# Board.net
KiCad netlist of a schematic drawn in EAGLE
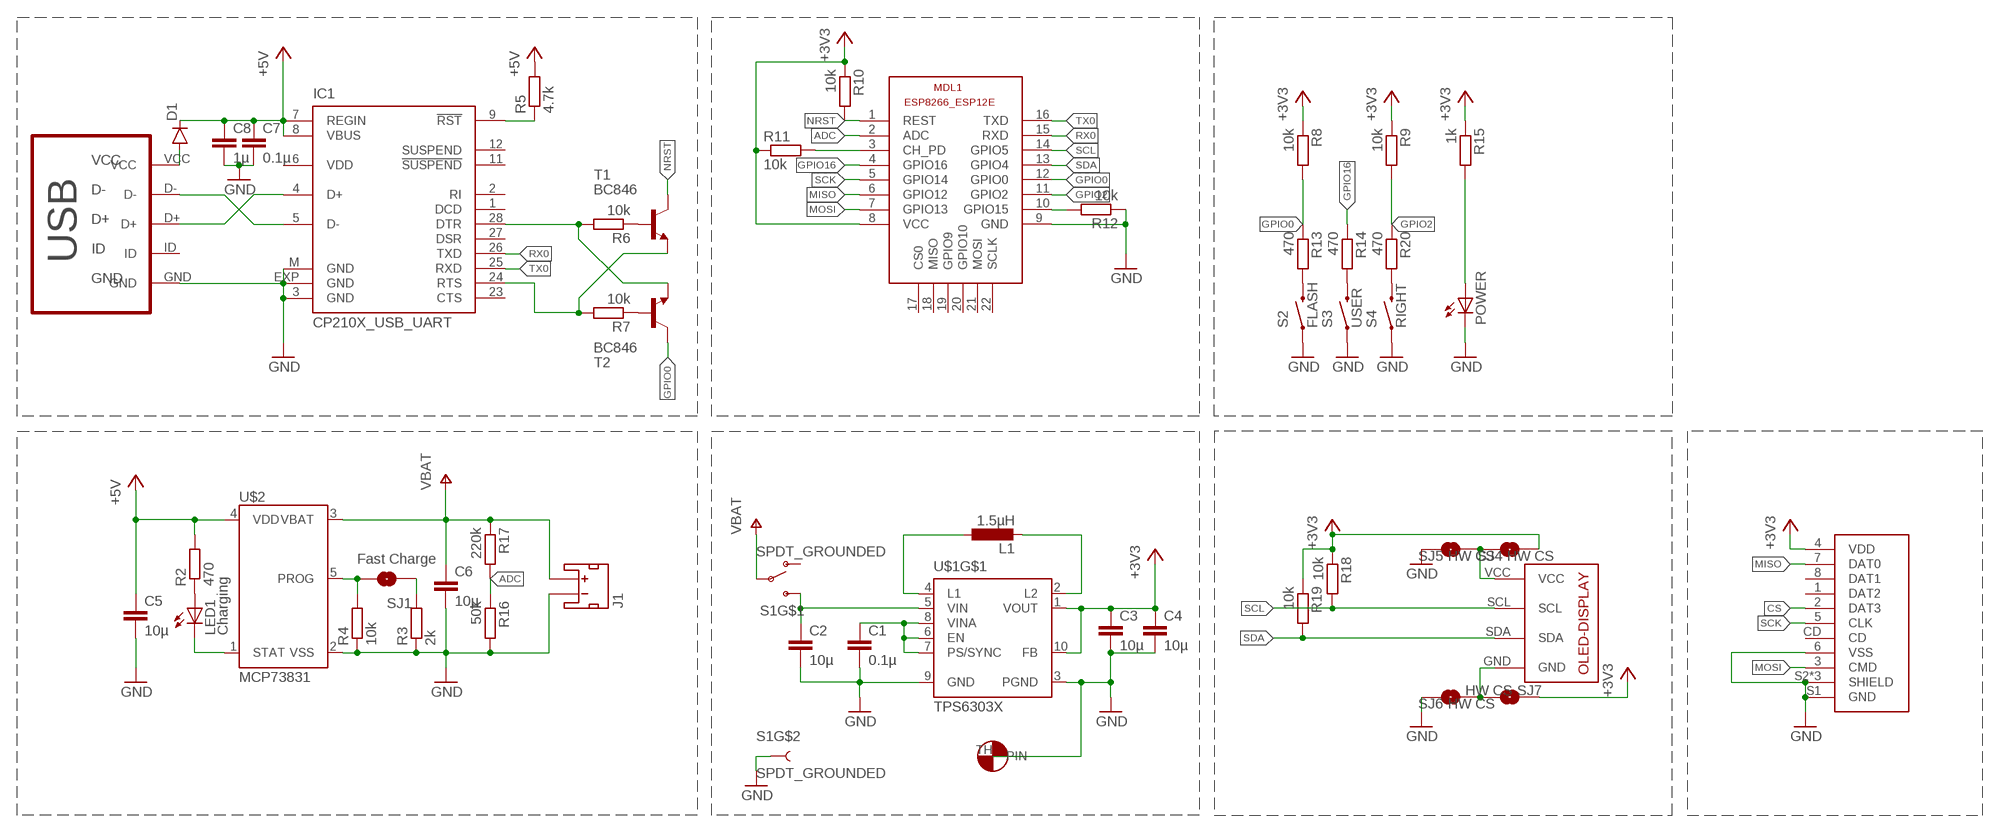
[diagram p0: schematic, sheet 1]

(export (version "E")
  (design (tool "Eeschema 10.0.6"))
  (components
    (comp (ref "C1")
      (value "0.1µ")
      (footprint "eagle-import:C0603")
      (libsource (lib "eagle-import") (part "C-EUC0603"))
    )
    (comp (ref "C2")
      (value "10µ")
      (footprint "eagle-import:C0603")
      (libsource (lib "eagle-import") (part "C-EUC0603"))
    )
    (comp (ref "C3")
      (value "10µ")
      (footprint "eagle-import:C0603")
      (libsource (lib "eagle-import") (part "C-EUC0603"))
    )
    (comp (ref "C4")
      (value "10µ")
      (footprint "eagle-import:C0603")
      (libsource (lib "eagle-import") (part "C-EUC0603"))
    )
    (comp (ref "C5")
      (value "10µ")
      (footprint "eagle-import:C0603")
      (libsource (lib "eagle-import") (part "C-EUC0603"))
    )
    (comp (ref "C6")
      (value "10µ")
      (footprint "eagle-import:C0603")
      (libsource (lib "eagle-import") (part "C-EUC0603"))
    )
    (comp (ref "C7")
      (value "0.1µ")
      (footprint "eagle-import:C0603")
      (libsource (lib "eagle-import") (part "C-EUC0603"))
    )
    (comp (ref "C8")
      (value "1µ")
      (footprint "eagle-import:C0603")
      (libsource (lib "eagle-import") (part "C-EUC0603"))
    )
    (comp (ref "D1")
      (value "DIODEBAS16")
      (footprint "eagle-import:SOD-323")
      (libsource (lib "eagle-import") (part "DIODEBAS16"))
    )
    (comp (ref "IC1")
      (value "CP210X_USB_UART")
      (footprint "eagle-import:MLP28")
      (libsource (lib "eagle-import") (part "CP210X_USB_UART"))
    )
    (comp (ref "J1")
      (value "JST_2MM_MALE")
      (footprint "eagle-import:JST-2-SMD")
      (libsource (lib "eagle-import") (part "JST_2MM_MALE"))
    )
    (comp (ref "L1")
      (value "1.5µH")
      (footprint "eagle-import:L3225P")
      (libsource (lib "eagle-import") (part "L-EUL3225P"))
    )
    (comp (ref "LED1")
      (value "Charging")
      (footprint "eagle-import:SML0805")
      (libsource (lib "eagle-import") (part "LEDSML0805"))
    )
    (comp (ref "MDL1")
      (value "ESP8266-12EESP8266-ESP12E")
      (footprint "eagle-import:ESP8266-ESP12E")
      (libsource (lib "eagle-import") (part "ESP8266-12EESP8266-ESP12E"))
    )
    (comp (ref "POWER")
      (value "LEDSML0805")
      (footprint "eagle-import:SML0805")
      (libsource (lib "eagle-import") (part "LEDSML0805"))
    )
    (comp (ref "R2")
      (value "470")
      (footprint "eagle-import:R0603")
      (libsource (lib "eagle-import") (part "R-EU_R0603"))
    )
    (comp (ref "R3")
      (value "2k")
      (footprint "eagle-import:R0603")
      (libsource (lib "eagle-import") (part "R-EU_R0603"))
    )
    (comp (ref "R4")
      (value "10k")
      (footprint "eagle-import:R0603")
      (libsource (lib "eagle-import") (part "R-EU_R0603"))
    )
    (comp (ref "R5")
      (value "4.7k")
      (footprint "eagle-import:R0603")
      (libsource (lib "eagle-import") (part "R-EU_R0603"))
    )
    (comp (ref "R6")
      (value "10k")
      (footprint "eagle-import:R0603")
      (libsource (lib "eagle-import") (part "R-EU_R0603"))
    )
    (comp (ref "R7")
      (value "10k")
      (footprint "eagle-import:R0603")
      (libsource (lib "eagle-import") (part "R-EU_R0603"))
    )
    (comp (ref "R8")
      (value "10k")
      (footprint "eagle-import:R0603")
      (libsource (lib "eagle-import") (part "R-EU_R0603"))
    )
    (comp (ref "R9")
      (value "10k")
      (footprint "eagle-import:R0603")
      (libsource (lib "eagle-import") (part "R-EU_R0603"))
    )
    (comp (ref "R10")
      (value "10k")
      (footprint "eagle-import:R0603")
      (libsource (lib "eagle-import") (part "R-EU_R0603"))
    )
    (comp (ref "R11")
      (value "10k")
      (footprint "eagle-import:R0603")
      (libsource (lib "eagle-import") (part "R-EU_R0603"))
    )
    (comp (ref "R12")
      (value "10k")
      (footprint "eagle-import:R0603")
      (libsource (lib "eagle-import") (part "R-EU_R0603"))
    )
    (comp (ref "R13")
      (value "470")
      (footprint "eagle-import:R0603")
      (libsource (lib "eagle-import") (part "R-EU_R0603"))
    )
    (comp (ref "R14")
      (value "470")
      (footprint "eagle-import:R0603")
      (libsource (lib "eagle-import") (part "R-EU_R0603"))
    )
    (comp (ref "R15")
      (value "1k")
      (footprint "eagle-import:R0603")
      (libsource (lib "eagle-import") (part "R-EU_R0603"))
    )
    (comp (ref "R16")
      (value "50k")
      (footprint "eagle-import:R0603")
      (libsource (lib "eagle-import") (part "R-EU_R0603"))
    )
    (comp (ref "R17")
      (value "220k")
      (footprint "eagle-import:R0603")
      (libsource (lib "eagle-import") (part "R-EU_R0603"))
    )
    (comp (ref "R18")
      (value "10k")
      (footprint "eagle-import:R0603")
      (libsource (lib "eagle-import") (part "R-EU_R0603"))
    )
    (comp (ref "R19")
      (value "10k")
      (footprint "eagle-import:R0603")
      (libsource (lib "eagle-import") (part "R-EU_R0603"))
    )
    (comp (ref "R20")
      (value "470")
      (footprint "eagle-import:R0603")
      (libsource (lib "eagle-import") (part "R-EU_R0603"))
    )
    (comp (ref "S1")
      (value "SPDT_GROUNDED")
      (footprint "eagle-import:SWITCH-SPST-SMD-A")
      (libsource (lib "eagle-import") (part "SPDT_GROUNDED"))
    )
    (comp (ref "S2")
      (value "FLASH")
      (footprint "eagle-import:TACTILE-SWITCH-1101NE")
      (libsource (lib "eagle-import") (part "SWITCH-MOMENTARY-2SMD-1101NE"))
    )
    (comp (ref "S3")
      (value "USER")
      (footprint "eagle-import:TACTILE-SWITCH-1101NE")
      (libsource (lib "eagle-import") (part "SWITCH-MOMENTARY-2SMD-1101NE"))
    )
    (comp (ref "S4")
      (value "RIGHT")
      (footprint "eagle-import:TACTILE-SWITCH-1101NE")
      (libsource (lib "eagle-import") (part "SWITCH-MOMENTARY-2SMD-1101NE"))
    )
    (comp (ref "SJ1")
      (value "Fast Charge")
      (footprint "eagle-import:SJ_2S-NO")
      (libsource (lib "eagle-import") (part "SOLDERJUMPERNO"))
    )
    (comp (ref "SJ4")
      (value "HW CS")
      (footprint "eagle-import:SJ_2S-NO")
      (libsource (lib "eagle-import") (part "SOLDERJUMPERNO"))
    )
    (comp (ref "SJ5")
      (value "HW CS")
      (footprint "eagle-import:SJ_2S-NO")
      (libsource (lib "eagle-import") (part "SOLDERJUMPERNO"))
    )
    (comp (ref "SJ6")
      (value "HW CS")
      (footprint "eagle-import:SJ_2S-NO")
      (libsource (lib "eagle-import") (part "SOLDERJUMPERNO"))
    )
    (comp (ref "SJ7")
      (value "HW CS")
      (footprint "eagle-import:SJ_2S-NO")
      (libsource (lib "eagle-import") (part "SOLDERJUMPERNO"))
    )
    (comp (ref "T1")
      (value "BC846")
      (footprint "eagle-import:SOT23")
      (libsource (lib "eagle-import") (part "BC846"))
    )
    (comp (ref "T2")
      (value "BC846")
      (footprint "eagle-import:SOT23")
      (libsource (lib "eagle-import") (part "BC846"))
    )
    (comp (ref "U$1")
      (value "TPS6303X")
      (footprint "eagle-import:DSK10")
      (libsource (lib "eagle-import") (part "TPS6303X"))
    )
    (comp (ref "U$2")
      (value "MCP73831")
      (footprint "eagle-import:SOT23-5")
      (libsource (lib "eagle-import") (part "MCP73831"))
    )
    (comp (ref "U$3")
      (value "MICRO-USB-B")
      (footprint "eagle-import:MICRO_USB_4_LEGS")
      (libsource (lib "eagle-import") (part "MICRO-USB-B"))
    )
    (comp (ref "U$4")
      (value "MICRO_SD_SOCKET")
      (footprint "eagle-import:MICRO_SD")
      (libsource (lib "eagle-import") (part "MICRO_SD_SOCKET"))
    )
    (comp (ref "U$6")
      (value "OLED-I2C")
      (footprint "eagle-import:OLED-I2C")
      (libsource (lib "eagle-import") (part "OLED-I2C"))
    )
  )
  (nets
    (net (code "1") (name "+3V3") (class "Default")
      (node (ref "C3") (pin "1") (pinfunction "1_1") (pintype "passive"))
      (node (ref "C4") (pin "1") (pinfunction "1_1") (pintype "passive"))
      (node (ref "MDL1") (pin "8") (pinfunction "VCC_8") (pintype "bidirectional"))
      (node (ref "R10") (pin "1") (pinfunction "1_1") (pintype "passive"))
      (node (ref "R11") (pin "1") (pinfunction "1_1") (pintype "passive"))
      (node (ref "R15") (pin "1") (pinfunction "1_1") (pintype "passive"))
      (node (ref "R18") (pin "1") (pinfunction "1_1") (pintype "passive"))
      (node (ref "R19") (pin "1") (pinfunction "1_1") (pintype "passive"))
      (node (ref "R8") (pin "1") (pinfunction "1_1") (pintype "passive"))
      (node (ref "R9") (pin "1") (pinfunction "1_1") (pintype "passive"))
      (node (ref "SJ4") (pin "1") (pinfunction "1_1") (pintype "passive"))
      (node (ref "SJ7") (pin "2") (pinfunction "2_2") (pintype "passive"))
      (node (ref "U$1") (pin "1") (pinfunction "VOUT_1") (pintype "output"))
      (node (ref "U$1") (pin "10") (pinfunction "FB_10") (pintype "input"))
      (node (ref "U$4") (pin "4") (pinfunction "VDD_4") (pintype "bidirectional"))
    )
    (net (code "2") (name "+5V") (class "Default")
      (node (ref "C5") (pin "1") (pinfunction "1_1") (pintype "passive"))
      (node (ref "C7") (pin "1") (pinfunction "1_1") (pintype "passive"))
      (node (ref "C8") (pin "1") (pinfunction "1_1") (pintype "passive"))
      (node (ref "D1") (pin "C") (pinfunction "C_C") (pintype "passive"))
      (node (ref "IC1") (pin "7") (pinfunction "REGIN_7") (pintype "passive"))
      (node (ref "IC1") (pin "8") (pinfunction "VBUS_8") (pintype "input"))
      (node (ref "R2") (pin "2") (pinfunction "2_2") (pintype "passive"))
      (node (ref "R5") (pin "2") (pinfunction "2_2") (pintype "passive"))
      (node (ref "U$2") (pin "4") (pinfunction "VDD_4") (pintype "power_in"))
    )
    (net (code "3") (name "/VDD") (class "Default")
      (node (ref "IC1") (pin "6") (pinfunction "VDD_6") (pintype "power_in"))
    )
    (net (code "4") (name "ADC") (class "Default")
      (node (ref "MDL1") (pin "2") (pinfunction "ADC_2") (pintype "bidirectional"))
      (node (ref "R16") (pin "1") (pinfunction "1_1") (pintype "passive"))
      (node (ref "R17") (pin "2") (pinfunction "2_2") (pintype "passive"))
    )
    (net (code "5") (name "CS") (class "Default")
      (node (ref "MDL1") (pin "10") (pinfunction "GPIO15_10") (pintype "bidirectional"))
      (node (ref "R12") (pin "2") (pinfunction "2_2") (pintype "passive"))
      (node (ref "U$4") (pin "2") (pinfunction "DAT3_2") (pintype "bidirectional"))
    )
    (net (code "6") (name "GND") (class "Default")
      (node (ref "C1") (pin "2") (pinfunction "2_2") (pintype "passive"))
      (node (ref "C2") (pin "2") (pinfunction "2_2") (pintype "passive"))
      (node (ref "C3") (pin "2") (pinfunction "2_2") (pintype "passive"))
      (node (ref "C4") (pin "2") (pinfunction "2_2") (pintype "passive"))
      (node (ref "C5") (pin "2") (pinfunction "2_2") (pintype "passive"))
      (node (ref "C6") (pin "2") (pinfunction "2_2") (pintype "passive"))
      (node (ref "C7") (pin "2") (pinfunction "2_2") (pintype "passive"))
      (node (ref "C8") (pin "2") (pinfunction "2_2") (pintype "passive"))
      (node (ref "IC1") (pin "3") (pinfunction "GND_3") (pintype "power_in"))
      (node (ref "IC1") (pin "EXP") (pinfunction "GND_EXP") (pintype "power_in"))
      (node (ref "IC1") (pin "M") (pinfunction "GND_M") (pintype "power_in"))
      (node (ref "J1") (pin "1") (pinfunction "-_1") (pintype "bidirectional"))
      (node (ref "MDL1") (pin "9") (pinfunction "GND_9") (pintype "bidirectional"))
      (node (ref "POWER") (pin "C") (pinfunction "C_C") (pintype "passive"))
      (node (ref "R12") (pin "1") (pinfunction "1_1") (pintype "passive"))
      (node (ref "R16") (pin "2") (pinfunction "2_2") (pintype "passive"))
      (node (ref "R3") (pin "1") (pinfunction "1_1") (pintype "passive"))
      (node (ref "R4") (pin "1") (pinfunction "1_1") (pintype "passive"))
      (node (ref "S1") (pin "GND1") (pinfunction "1_GND1") (pintype "bidirectional"))
      (node (ref "S1") (pin "GND2") (pinfunction "1_GND2") (pintype "bidirectional"))
      (node (ref "S1") (pin "GND3") (pinfunction "1_GND3") (pintype "bidirectional"))
      (node (ref "S1") (pin "GND4") (pinfunction "1_GND4") (pintype "bidirectional"))
      (node (ref "S2") (pin "1") (pinfunction "1_1") (pintype "passive"))
      (node (ref "S3") (pin "1") (pinfunction "1_1") (pintype "passive"))
      (node (ref "S4") (pin "1") (pinfunction "1_1") (pintype "passive"))
      (node (ref "SJ5") (pin "2") (pinfunction "2_2") (pintype "passive"))
      (node (ref "SJ6") (pin "2") (pinfunction "2_2") (pintype "passive"))
      (node (ref "U$1") (pin "3") (pinfunction "PGND_3") (pintype "power_in"))
      (node (ref "U$1") (pin "9") (pinfunction "GND_9") (pintype "power_in"))
      (node (ref "U$1") (pin "TH") (pinfunction "PIN_TH") (pintype "bidirectional"))
      (node (ref "U$2") (pin "2") (pinfunction "VSS_2") (pintype "power_in"))
      (node (ref "U$3") (pin "GND") (pinfunction "GND_GND") (pintype "bidirectional"))
      (node (ref "U$4") (pin "6") (pinfunction "VSS_6") (pintype "bidirectional"))
      (node (ref "U$4") (pin "S1") (pinfunction "GND_S1") (pintype "bidirectional"))
      (node (ref "U$4") (pin "S2") (pinfunction "SHIELD_S2") (pintype "bidirectional"))
      (node (ref "U$4") (pin "S3") (pinfunction "SHIELD_S3") (pintype "bidirectional"))
      (node (ref "U$4") (pin "S4") (pinfunction "SHIELD_S4") (pintype "bidirectional"))
    )
    (net (code "7") (name "GPIO0") (class "Default")
      (node (ref "MDL1") (pin "12") (pinfunction "GPIO0_12") (pintype "bidirectional"))
      (node (ref "R13") (pin "1") (pinfunction "1_1") (pintype "passive"))
      (node (ref "R8") (pin "2") (pinfunction "2_2") (pintype "passive"))
      (node (ref "T2") (pin "3") (pinfunction "C_3") (pintype "passive"))
    )
    (net (code "8") (name "GPIO2") (class "Default")
      (node (ref "MDL1") (pin "11") (pinfunction "GPIO2_11") (pintype "bidirectional"))
      (node (ref "R20") (pin "1") (pinfunction "1_1") (pintype "passive"))
      (node (ref "R9") (pin "2") (pinfunction "2_2") (pintype "passive"))
    )
    (net (code "9") (name "GPIO16") (class "Default")
      (node (ref "MDL1") (pin "4") (pinfunction "GPIO16_4") (pintype "bidirectional"))
      (node (ref "R14") (pin "1") (pinfunction "1_1") (pintype "passive"))
    )
    (net (code "10") (name "MISO") (class "Default")
      (node (ref "MDL1") (pin "6") (pinfunction "GPIO12_6") (pintype "bidirectional"))
      (node (ref "U$4") (pin "7") (pinfunction "DAT0_7") (pintype "bidirectional"))
    )
    (net (code "11") (name "MOSI") (class "Default")
      (node (ref "MDL1") (pin "7") (pinfunction "GPIO13_7") (pintype "bidirectional"))
      (node (ref "U$4") (pin "3") (pinfunction "CMD_3") (pintype "bidirectional"))
    )
    (net (code "12") (name "NRST") (class "Default")
      (node (ref "MDL1") (pin "1") (pinfunction "REST_1") (pintype "bidirectional"))
      (node (ref "R10") (pin "2") (pinfunction "2_2") (pintype "passive"))
      (node (ref "T1") (pin "3") (pinfunction "C_3") (pintype "passive"))
    )
    (net (code "13") (name "Net-(D1-PadA)") (class "Default")
      (node (ref "D1") (pin "A") (pinfunction "A_A") (pintype "passive"))
      (node (ref "U$3") (pin "VCC") (pinfunction "VCC_VCC") (pintype "bidirectional"))
    )
    (net (code "14") (name "Net-(IC1-D+)") (class "Default")
      (node (ref "IC1") (pin "4") (pinfunction "D+_4") (pintype "bidirectional"))
      (node (ref "U$3") (pin "D+") (pinfunction "D+_D+") (pintype "bidirectional"))
    )
    (net (code "15") (name "Net-(IC1-D-)") (class "Default")
      (node (ref "IC1") (pin "5") (pinfunction "D-_5") (pintype "bidirectional"))
      (node (ref "U$3") (pin "D-") (pinfunction "D-_D-") (pintype "bidirectional"))
    )
    (net (code "16") (name "Net-(IC1-DTR)") (class "Default")
      (node (ref "IC1") (pin "28") (pinfunction "DTR_28") (pintype "output"))
      (node (ref "R6") (pin "2") (pinfunction "2_2") (pintype "passive"))
      (node (ref "T2") (pin "2") (pinfunction "E_2") (pintype "passive"))
    )
    (net (code "17") (name "Net-(IC1-RTS)") (class "Default")
      (node (ref "IC1") (pin "24") (pinfunction "RTS_24") (pintype "output"))
      (node (ref "R7") (pin "2") (pinfunction "2_2") (pintype "passive"))
      (node (ref "T1") (pin "2") (pinfunction "E_2") (pintype "passive"))
    )
    (net (code "18") (name "Net-(IC1-~{RST})") (class "Default")
      (node (ref "IC1") (pin "9") (pinfunction "~{RST}_9") (pintype "bidirectional"))
      (node (ref "R5") (pin "1") (pinfunction "1_1") (pintype "passive"))
    )
    (net (code "19") (name "Net-(LED1-PadA)") (class "Default")
      (node (ref "LED1") (pin "A") (pinfunction "A_A") (pintype "passive"))
      (node (ref "R2") (pin "1") (pinfunction "1_1") (pintype "passive"))
    )
    (net (code "20") (name "Net-(MDL1-CH_PD)") (class "Default")
      (node (ref "MDL1") (pin "3") (pinfunction "CH_PD_3") (pintype "bidirectional"))
      (node (ref "R11") (pin "2") (pinfunction "2_2") (pintype "passive"))
    )
    (net (code "21") (name "Net-(POWER-PadA)") (class "Default")
      (node (ref "POWER") (pin "A") (pinfunction "A_A") (pintype "passive"))
      (node (ref "R15") (pin "2") (pinfunction "2_2") (pintype "passive"))
    )
    (net (code "22") (name "Net-(R3-Pad2)") (class "Default")
      (node (ref "R3") (pin "2") (pinfunction "2_2") (pintype "passive"))
      (node (ref "SJ1") (pin "2") (pinfunction "2_2") (pintype "passive"))
    )
    (net (code "23") (name "Net-(R13-Pad2)") (class "Default")
      (node (ref "R13") (pin "2") (pinfunction "2_2") (pintype "passive"))
      (node (ref "S2") (pin "2") (pinfunction "2_2") (pintype "passive"))
    )
    (net (code "24") (name "Net-(R14-Pad2)") (class "Default")
      (node (ref "R14") (pin "2") (pinfunction "2_2") (pintype "passive"))
      (node (ref "S3") (pin "2") (pinfunction "2_2") (pintype "passive"))
    )
    (net (code "25") (name "Net-(R20-Pad2)") (class "Default")
      (node (ref "R20") (pin "2") (pinfunction "2_2") (pintype "passive"))
      (node (ref "S4") (pin "2") (pinfunction "2_2") (pintype "passive"))
    )
    (net (code "26") (name "Net-(S1A-S)") (class "Default")
      (node (ref "C2") (pin "1") (pinfunction "1_1") (pintype "passive"))
      (node (ref "S1") (pin "3") (pinfunction "S_3") (pintype "passive"))
      (node (ref "U$1") (pin "5") (pinfunction "VIN_5") (pintype "input"))
    )
    (net (code "27") (name "Net-(SJ4-Pad2)") (class "Default")
      (node (ref "SJ4") (pin "2") (pinfunction "2_2") (pintype "passive"))
      (node (ref "SJ5") (pin "1") (pinfunction "1_1") (pintype "passive"))
      (node (ref "U$6") (pin "VCC") (pinfunction "VCC_VCC") (pintype "bidirectional"))
    )
    (net (code "28") (name "Net-(SJ6-Pad1)") (class "Default")
      (node (ref "SJ6") (pin "1") (pinfunction "1_1") (pintype "passive"))
      (node (ref "SJ7") (pin "1") (pinfunction "1_1") (pintype "passive"))
      (node (ref "U$6") (pin "GND") (pinfunction "GND_GND") (pintype "bidirectional"))
    )
    (net (code "29") (name "Net-(T1-B)") (class "Default")
      (node (ref "R6") (pin "1") (pinfunction "1_1") (pintype "passive"))
      (node (ref "T1") (pin "1") (pinfunction "B_1") (pintype "passive"))
    )
    (net (code "30") (name "Net-(T2-B)") (class "Default")
      (node (ref "R7") (pin "1") (pinfunction "1_1") (pintype "passive"))
      (node (ref "T2") (pin "1") (pinfunction "B_1") (pintype "passive"))
    )
    (net (code "31") (name "Net-(U$1A-EN)") (class "Default")
      (node (ref "C1") (pin "1") (pinfunction "1_1") (pintype "passive"))
      (node (ref "U$1") (pin "6") (pinfunction "EN_6") (pintype "input"))
      (node (ref "U$1") (pin "7") (pinfunction "PS/SYNC_7") (pintype "input"))
      (node (ref "U$1") (pin "8") (pinfunction "VINA_8") (pintype "input"))
    )
    (net (code "32") (name "Net-(U$1A-L1)") (class "Default")
      (node (ref "L1") (pin "1") (pinfunction "1_1") (pintype "passive"))
      (node (ref "U$1") (pin "4") (pinfunction "L1_4") (pintype "passive"))
    )
    (net (code "33") (name "Net-(U$1A-L2)") (class "Default")
      (node (ref "L1") (pin "2") (pinfunction "2_2") (pintype "passive"))
      (node (ref "U$1") (pin "2") (pinfunction "L2_2") (pintype "passive"))
    )
    (net (code "34") (name "Net-(U$2-PROG)") (class "Default")
      (node (ref "R4") (pin "2") (pinfunction "2_2") (pintype "passive"))
      (node (ref "SJ1") (pin "1") (pinfunction "1_1") (pintype "passive"))
      (node (ref "U$2") (pin "5") (pinfunction "PROG_5") (pintype "input"))
    )
    (net (code "35") (name "Net-(U$2-STAT)") (class "Default")
      (node (ref "LED1") (pin "C") (pinfunction "C_C") (pintype "passive"))
      (node (ref "U$2") (pin "1") (pinfunction "STAT_1") (pintype "output"))
    )
    (net (code "36") (name "RX0") (class "Default")
      (node (ref "IC1") (pin "26") (pinfunction "TXD_26") (pintype "output"))
      (node (ref "MDL1") (pin "15") (pinfunction "RXD_15") (pintype "bidirectional"))
    )
    (net (code "37") (name "SCK") (class "Default")
      (node (ref "MDL1") (pin "5") (pinfunction "GPIO14_5") (pintype "bidirectional"))
      (node (ref "U$4") (pin "5") (pinfunction "CLK_5") (pintype "bidirectional"))
    )
    (net (code "38") (name "SCL") (class "Default")
      (node (ref "MDL1") (pin "14") (pinfunction "GPIO5_14") (pintype "bidirectional"))
      (node (ref "R18") (pin "2") (pinfunction "2_2") (pintype "passive"))
      (node (ref "U$6") (pin "SCL") (pinfunction "SCL_SCL") (pintype "bidirectional"))
    )
    (net (code "39") (name "SDA") (class "Default")
      (node (ref "MDL1") (pin "13") (pinfunction "GPIO4_13") (pintype "bidirectional"))
      (node (ref "R19") (pin "2") (pinfunction "2_2") (pintype "passive"))
      (node (ref "U$6") (pin "SDA") (pinfunction "SDA_SDA") (pintype "bidirectional"))
    )
    (net (code "40") (name "TX0") (class "Default")
      (node (ref "IC1") (pin "25") (pinfunction "RXD_25") (pintype "input"))
      (node (ref "MDL1") (pin "16") (pinfunction "TXD_16") (pintype "bidirectional"))
    )
    (net (code "41") (name "VBAT") (class "Default")
      (node (ref "C6") (pin "1") (pinfunction "1_1") (pintype "passive"))
      (node (ref "J1") (pin "2") (pinfunction "+_2") (pintype "bidirectional"))
      (node (ref "R17") (pin "1") (pinfunction "1_1") (pintype "passive"))
      (node (ref "S1") (pin "2") (pinfunction "P_2") (pintype "passive"))
      (node (ref "U$2") (pin "3") (pinfunction "VBAT_3") (pintype "power_in"))
    )
    (net (code "42") (name "unconnected-(IC1-CTS-Pad23)") (class "Default")
      (node (ref "IC1") (pin "23") (pinfunction "CTS_23") (pintype "input"))
    )
    (net (code "43") (name "unconnected-(IC1-DCD-Pad1)") (class "Default")
      (node (ref "IC1") (pin "1") (pinfunction "DCD_1") (pintype "input"))
    )
    (net (code "44") (name "unconnected-(IC1-DSR-Pad27)") (class "Default")
      (node (ref "IC1") (pin "27") (pinfunction "DSR_27") (pintype "input"))
    )
    (net (code "45") (name "unconnected-(IC1-RI-Pad2)") (class "Default")
      (node (ref "IC1") (pin "2") (pinfunction "RI_2") (pintype "input"))
    )
    (net (code "46") (name "unconnected-(IC1-SUSPEND-Pad12)") (class "Default")
      (node (ref "IC1") (pin "12") (pinfunction "SUSPEND_12") (pintype "output"))
    )
    (net (code "47") (name "unconnected-(IC1-~{SUSPEND}-Pad11)") (class "Default")
      (node (ref "IC1") (pin "11") (pinfunction "~{SUSPEND}_11") (pintype "output"))
    )
    (net (code "48") (name "unconnected-(J1-PAD1-PadNC1)") (class "Default")
      (node (ref "J1") (pin "NC1") (pinfunction "PAD1_NC1") (pintype "bidirectional"))
    )
    (net (code "49") (name "unconnected-(J1-PAD2-PadNC2)") (class "Default")
      (node (ref "J1") (pin "NC2") (pinfunction "PAD2_NC2") (pintype "bidirectional"))
    )
    (net (code "50") (name "unconnected-(MDL1-CS0-Pad17)") (class "Default")
      (node (ref "MDL1") (pin "17") (pinfunction "CS0_17") (pintype "bidirectional"))
    )
    (net (code "51") (name "unconnected-(MDL1-GPIO9-Pad19)") (class "Default")
      (node (ref "MDL1") (pin "19") (pinfunction "GPIO9_19") (pintype "bidirectional"))
    )
    (net (code "52") (name "unconnected-(MDL1-GPIO10-Pad20)") (class "Default")
      (node (ref "MDL1") (pin "20") (pinfunction "GPIO10_20") (pintype "bidirectional"))
    )
    (net (code "53") (name "unconnected-(MDL1-MISO-Pad18)") (class "Default")
      (node (ref "MDL1") (pin "18") (pinfunction "MISO_18") (pintype "bidirectional"))
    )
    (net (code "54") (name "unconnected-(MDL1-MOSI-Pad21)") (class "Default")
      (node (ref "MDL1") (pin "21") (pinfunction "MOSI_21") (pintype "bidirectional"))
    )
    (net (code "55") (name "unconnected-(MDL1-SCLK-Pad22)") (class "Default")
      (node (ref "MDL1") (pin "22") (pinfunction "SCLK_22") (pintype "bidirectional"))
    )
    (net (code "56") (name "unconnected-(S1A-O-Pad1)") (class "Default")
      (node (ref "S1") (pin "1") (pinfunction "O_1") (pintype "passive"))
    )
    (net (code "57") (name "unconnected-(U$3-PadID)") (class "Default")
      (node (ref "U$3") (pin "ID") (pinfunction "ID_ID") (pintype "bidirectional"))
    )
    (net (code "58") (name "unconnected-(U$4-DAT1-Pad8)") (class "Default")
      (node (ref "U$4") (pin "8") (pinfunction "DAT1_8") (pintype "bidirectional"))
    )
    (net (code "59") (name "unconnected-(U$4-DAT2-Pad1)") (class "Default")
      (node (ref "U$4") (pin "1") (pinfunction "DAT2_1") (pintype "bidirectional"))
    )
    (net (code "60") (name "unconnected-(U$4-PadCD)") (class "Default")
      (node (ref "U$4") (pin "CD") (pinfunction "CD_CD") (pintype "bidirectional"))
    )
  )
)
